# Puzzle_Joystick_v1_0.net
KiCad netlist of a schematic drawn in EAGLE
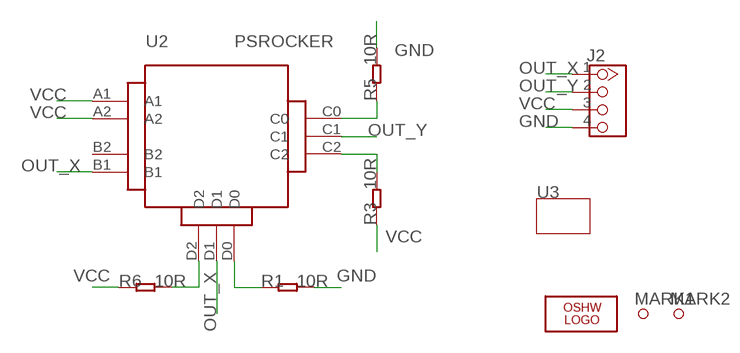
[diagram p0: schematic, sheet 1]

(export (version "E")
  (design (tool "Eeschema 10.0.6"))
  (components
    (comp (ref "J2")
      (value "TWIG-2.0-LEADED")
      (footprint "eagle-import:4P-LEADED-2.0")
      (libsource (lib "eagle-import") (part "TWIG-2.0-LEADED"))
    )
    (comp (ref "LOGO1")
      (value "LOGO-OSHW-FILLX0150-NT")
      (footprint "eagle-import:OSHW_FILLX150_NOTEXT")
      (libsource (lib "eagle-import") (part "LOGO-OSHW-FILLX0150-NT"))
    )
    (comp (ref "MARK1")
      (value "PAD-MARK")
      (footprint "eagle-import:MARK")
      (libsource (lib "eagle-import") (part "PAD-MARK"))
    )
    (comp (ref "MARK2")
      (value "PAD-MARK")
      (footprint "eagle-import:MARK")
      (libsource (lib "eagle-import") (part "PAD-MARK"))
    )
    (comp (ref "R1")
      (value "10R")
      (footprint "eagle-import:0603")
      (libsource (lib "eagle-import") (part "R-0603"))
    )
    (comp (ref "R3")
      (value "10R")
      (footprint "eagle-import:0603")
      (libsource (lib "eagle-import") (part "R-0603"))
    )
    (comp (ref "R5")
      (value "10R")
      (footprint "eagle-import:0603")
      (libsource (lib "eagle-import") (part "R-0603"))
    )
    (comp (ref "R6")
      (value "10R")
      (footprint "eagle-import:0603")
      (libsource (lib "eagle-import") (part "R-0603"))
    )
    (comp (ref "U2")
      (value "PSROCKER")
      (footprint "eagle-import:PSROCKER")
      (libsource (lib "eagle-import") (part "PSROCKER"))
    )
    (comp (ref "U3")
      (value "TWIG-2U")
      (footprint "eagle-import:2U-DIM-W_-DRILL")
      (libsource (lib "eagle-import") (part "TWIG-2U"))
    )
  )
  (nets
    (net (code "1") (name "/GND") (class "Default")
      (node (ref "J2") (pin "4") (pinfunction "4_4") (pintype "bidirectional"))
      (node (ref "R1") (pin "2") (pinfunction "2_2") (pintype "passive"))
      (node (ref "R5") (pin "2") (pinfunction "2_2") (pintype "passive"))
    )
    (net (code "2") (name "/OUT_X") (class "Default")
      (node (ref "J2") (pin "1") (pinfunction "1_1") (pintype "bidirectional"))
      (node (ref "U2") (pin "B1") (pinfunction "B1_B1") (pintype "bidirectional"))
      (node (ref "U2") (pin "D1") (pinfunction "D1_D1") (pintype "bidirectional"))
    )
    (net (code "3") (name "/OUT_Y") (class "Default")
      (node (ref "J2") (pin "2") (pinfunction "2_2") (pintype "bidirectional"))
      (node (ref "U2") (pin "C1") (pinfunction "C1_C1") (pintype "bidirectional"))
    )
    (net (code "4") (name "/VCC") (class "Default")
      (node (ref "J2") (pin "3") (pinfunction "3_3") (pintype "bidirectional"))
      (node (ref "R3") (pin "1") (pinfunction "1_1") (pintype "passive"))
      (node (ref "R6") (pin "1") (pinfunction "1_1") (pintype "passive"))
      (node (ref "U2") (pin "A1") (pinfunction "A1_A1") (pintype "bidirectional"))
      (node (ref "U2") (pin "A2") (pinfunction "A2_A2") (pintype "bidirectional"))
    )
    (net (code "5") (name "Net-(R1-Pad1)") (class "Default")
      (node (ref "R1") (pin "1") (pinfunction "1_1") (pintype "passive"))
      (node (ref "U2") (pin "D0") (pinfunction "D0_D0") (pintype "bidirectional"))
    )
    (net (code "6") (name "Net-(R3-Pad2)") (class "Default")
      (node (ref "R3") (pin "2") (pinfunction "2_2") (pintype "passive"))
      (node (ref "U2") (pin "C2") (pinfunction "C2_C2") (pintype "bidirectional"))
    )
    (net (code "7") (name "Net-(R5-Pad1)") (class "Default")
      (node (ref "R5") (pin "1") (pinfunction "1_1") (pintype "passive"))
      (node (ref "U2") (pin "C0") (pinfunction "C0_C0") (pintype "bidirectional"))
    )
    (net (code "8") (name "Net-(R6-Pad2)") (class "Default")
      (node (ref "R6") (pin "2") (pinfunction "2_2") (pintype "passive"))
      (node (ref "U2") (pin "D2") (pinfunction "D2_D2") (pintype "bidirectional"))
    )
    (net (code "9") (name "unconnected-(U2-PadB2)") (class "Default")
      (node (ref "U2") (pin "B2") (pinfunction "B2_B2") (pintype "bidirectional"))
    )
  )
)
